# controller.net
KiCad netlist of a schematic drawn in EAGLE
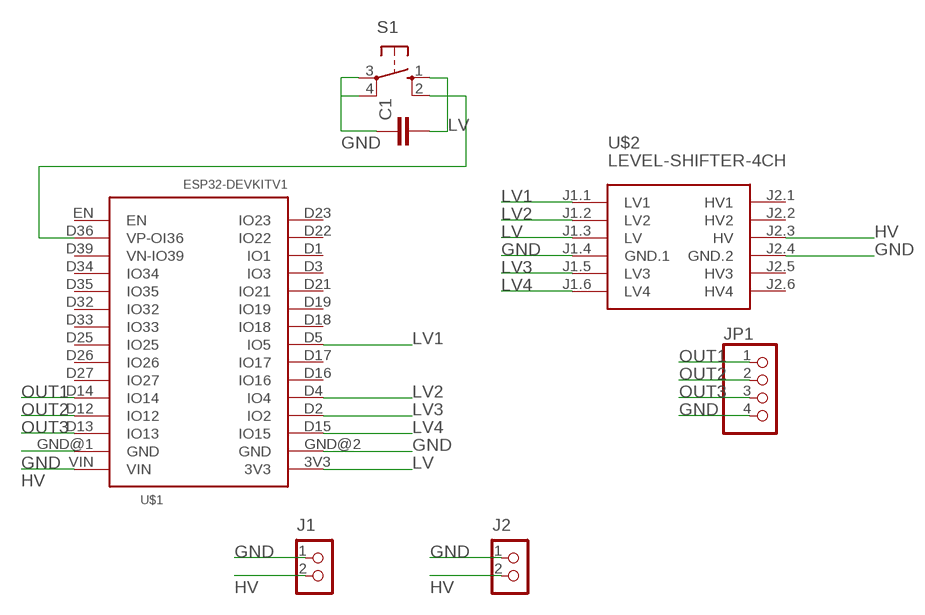
[diagram p0: schematic, sheet 1]

(export (version "E")
  (design (tool "Eeschema 10.0.6"))
  (components
    (comp (ref "C1")
      (value "C-EU025-025X050")
      (footprint "eagle-import:C025-025X050")
      (libsource (lib "eagle-import") (part "C-EU025-025X050"))
    )
    (comp (ref "J1")
      (value "CON_TERMINAL_BLOCK_02-5MM")
      (footprint "eagle-import:TERMINAL_BLOCK_2P_5")
      (libsource (lib "eagle-import") (part "CON_TERMINAL_BLOCK_02-5MM"))
    )
    (comp (ref "J2")
      (value "CON_TERMINAL_BLOCK_02-5MM")
      (footprint "eagle-import:TERMINAL_BLOCK_2P_5")
      (libsource (lib "eagle-import") (part "CON_TERMINAL_BLOCK_02-5MM"))
    )
    (comp (ref "JP1")
      (value "PINHD-1X4")
      (footprint "eagle-import:1X04")
      (libsource (lib "eagle-import") (part "PINHD-1X4"))
    )
    (comp (ref "S1")
      (value "10-XX")
      (footprint "eagle-import:B3F-10XX")
      (fields (field (name "MPN") "B3F-1000"))
      (libsource (lib "eagle-import") (part "10-XX"))
    )
    (comp (ref "U$1")
      (value "ESP32DEVKITV1")
      (footprint "eagle-import:ESP32-DEVKITV1")
      (libsource (lib "eagle-import") (part "ESP32DEVKITV1"))
    )
    (comp (ref "U$2")
      (value "LEVEL-SHIFTER-4CH")
      (footprint "eagle-import:LEVEL-SHIFTER-4CH")
      (libsource (lib "eagle-import") (part "LEVEL-SHIFTER-4CH"))
    )
  )
  (nets
    (net (code "1") (name "/GND") (class "Default")
      (node (ref "C1") (pin "1") (pinfunction "1_1") (pintype "passive"))
      (node (ref "J1") (pin "1") (pinfunction "1_1") (pintype "passive"))
      (node (ref "J2") (pin "1") (pinfunction "1_1") (pintype "passive"))
      (node (ref "JP1") (pin "4") (pinfunction "4_4") (pintype "passive"))
      (node (ref "S1") (pin "3") (pinfunction "P_3") (pintype "passive"))
      (node (ref "S1") (pin "4") (pinfunction "P1_4") (pintype "passive"))
      (node (ref "U$1") (pin "GND@1") (pinfunction "GND_GND@1") (pintype "bidirectional"))
      (node (ref "U$1") (pin "GND@2") (pinfunction "GND_GND@2") (pintype "bidirectional"))
      (node (ref "U$2") (pin "J1.4") (pinfunction "GND.1_J1.4") (pintype "power_in"))
      (node (ref "U$2") (pin "J2.4") (pinfunction "GND.2_J2.4") (pintype "power_in"))
    )
    (net (code "2") (name "/HV") (class "Default")
      (node (ref "J1") (pin "2") (pinfunction "2_2") (pintype "passive"))
      (node (ref "J2") (pin "2") (pinfunction "2_2") (pintype "passive"))
      (node (ref "U$1") (pin "VIN") (pinfunction "VIN_VIN") (pintype "bidirectional"))
      (node (ref "U$2") (pin "J2.3") (pinfunction "HV_J2.3") (pintype "power_in"))
    )
    (net (code "3") (name "/LV") (class "Default")
      (node (ref "C1") (pin "2") (pinfunction "2_2") (pintype "passive"))
      (node (ref "S1") (pin "1") (pinfunction "S_1") (pintype "passive"))
      (node (ref "S1") (pin "2") (pinfunction "S1_2") (pintype "passive"))
      (node (ref "U$1") (pin "3V3") (pinfunction "3V3_3V3") (pintype "bidirectional"))
      (node (ref "U$1") (pin "D36") (pinfunction "VP-OI36_D36") (pintype "bidirectional"))
      (node (ref "U$2") (pin "J1.3") (pinfunction "LV_J1.3") (pintype "power_in"))
    )
    (net (code "4") (name "/LV1") (class "Default")
      (node (ref "U$1") (pin "D5") (pinfunction "IO5_D5") (pintype "bidirectional"))
      (node (ref "U$2") (pin "J1.1") (pinfunction "LV1_J1.1") (pintype "bidirectional"))
    )
    (net (code "5") (name "/LV2") (class "Default")
      (node (ref "U$1") (pin "D4") (pinfunction "IO4_D4") (pintype "bidirectional"))
      (node (ref "U$2") (pin "J1.2") (pinfunction "LV2_J1.2") (pintype "bidirectional"))
    )
    (net (code "6") (name "/LV3") (class "Default")
      (node (ref "U$1") (pin "D2") (pinfunction "IO2_D2") (pintype "bidirectional"))
      (node (ref "U$2") (pin "J1.5") (pinfunction "LV3_J1.5") (pintype "bidirectional"))
    )
    (net (code "7") (name "/LV4") (class "Default")
      (node (ref "U$1") (pin "D15") (pinfunction "IO15_D15") (pintype "bidirectional"))
      (node (ref "U$2") (pin "J1.6") (pinfunction "LV4_J1.6") (pintype "bidirectional"))
    )
    (net (code "8") (name "/OUT1") (class "Default")
      (node (ref "JP1") (pin "1") (pinfunction "1_1") (pintype "passive"))
      (node (ref "U$1") (pin "D14") (pinfunction "IO14_D14") (pintype "bidirectional"))
    )
    (net (code "9") (name "/OUT2") (class "Default")
      (node (ref "JP1") (pin "2") (pinfunction "2_2") (pintype "passive"))
      (node (ref "U$1") (pin "D12") (pinfunction "IO12_D12") (pintype "bidirectional"))
    )
    (net (code "10") (name "/OUT3") (class "Default")
      (node (ref "JP1") (pin "3") (pinfunction "3_3") (pintype "passive"))
      (node (ref "U$1") (pin "D13") (pinfunction "IO13_D13") (pintype "bidirectional"))
    )
    (net (code "11") (name "unconnected-(U$1-IO1-PadD1)") (class "Default")
      (node (ref "U$1") (pin "D1") (pinfunction "IO1_D1") (pintype "bidirectional"))
    )
    (net (code "12") (name "unconnected-(U$1-IO3-PadD3)") (class "Default")
      (node (ref "U$1") (pin "D3") (pinfunction "IO3_D3") (pintype "bidirectional"))
    )
    (net (code "13") (name "unconnected-(U$1-IO16-PadD16)") (class "Default")
      (node (ref "U$1") (pin "D16") (pinfunction "IO16_D16") (pintype "bidirectional"))
    )
    (net (code "14") (name "unconnected-(U$1-IO17-PadD17)") (class "Default")
      (node (ref "U$1") (pin "D17") (pinfunction "IO17_D17") (pintype "bidirectional"))
    )
    (net (code "15") (name "unconnected-(U$1-IO18-PadD18)") (class "Default")
      (node (ref "U$1") (pin "D18") (pinfunction "IO18_D18") (pintype "bidirectional"))
    )
    (net (code "16") (name "unconnected-(U$1-IO19-PadD19)") (class "Default")
      (node (ref "U$1") (pin "D19") (pinfunction "IO19_D19") (pintype "bidirectional"))
    )
    (net (code "17") (name "unconnected-(U$1-IO21-PadD21)") (class "Default")
      (node (ref "U$1") (pin "D21") (pinfunction "IO21_D21") (pintype "bidirectional"))
    )
    (net (code "18") (name "unconnected-(U$1-IO22-PadD22)") (class "Default")
      (node (ref "U$1") (pin "D22") (pinfunction "IO22_D22") (pintype "bidirectional"))
    )
    (net (code "19") (name "unconnected-(U$1-IO23-PadD23)") (class "Default")
      (node (ref "U$1") (pin "D23") (pinfunction "IO23_D23") (pintype "bidirectional"))
    )
    (net (code "20") (name "unconnected-(U$1-IO25-PadD25)") (class "Default")
      (node (ref "U$1") (pin "D25") (pinfunction "IO25_D25") (pintype "bidirectional"))
    )
    (net (code "21") (name "unconnected-(U$1-IO26-PadD26)") (class "Default")
      (node (ref "U$1") (pin "D26") (pinfunction "IO26_D26") (pintype "bidirectional"))
    )
    (net (code "22") (name "unconnected-(U$1-IO27-PadD27)") (class "Default")
      (node (ref "U$1") (pin "D27") (pinfunction "IO27_D27") (pintype "bidirectional"))
    )
    (net (code "23") (name "unconnected-(U$1-IO32-PadD32)") (class "Default")
      (node (ref "U$1") (pin "D32") (pinfunction "IO32_D32") (pintype "bidirectional"))
    )
    (net (code "24") (name "unconnected-(U$1-IO33-PadD33)") (class "Default")
      (node (ref "U$1") (pin "D33") (pinfunction "IO33_D33") (pintype "bidirectional"))
    )
    (net (code "25") (name "unconnected-(U$1-IO34-PadD34)") (class "Default")
      (node (ref "U$1") (pin "D34") (pinfunction "IO34_D34") (pintype "bidirectional"))
    )
    (net (code "26") (name "unconnected-(U$1-IO35-PadD35)") (class "Default")
      (node (ref "U$1") (pin "D35") (pinfunction "IO35_D35") (pintype "bidirectional"))
    )
    (net (code "27") (name "unconnected-(U$1-PadEN)") (class "Default")
      (node (ref "U$1") (pin "EN") (pinfunction "EN_EN") (pintype "bidirectional"))
    )
    (net (code "28") (name "unconnected-(U$1-VN-IO39-PadD39)") (class "Default")
      (node (ref "U$1") (pin "D39") (pinfunction "VN-IO39_D39") (pintype "bidirectional"))
    )
    (net (code "29") (name "unconnected-(U$2-HV1-PadJ2.1)") (class "Default")
      (node (ref "U$2") (pin "J2.1") (pinfunction "HV1_J2.1") (pintype "bidirectional"))
    )
    (net (code "30") (name "unconnected-(U$2-HV2-PadJ2.2)") (class "Default")
      (node (ref "U$2") (pin "J2.2") (pinfunction "HV2_J2.2") (pintype "bidirectional"))
    )
    (net (code "31") (name "unconnected-(U$2-HV3-PadJ2.5)") (class "Default")
      (node (ref "U$2") (pin "J2.5") (pinfunction "HV3_J2.5") (pintype "bidirectional"))
    )
    (net (code "32") (name "unconnected-(U$2-HV4-PadJ2.6)") (class "Default")
      (node (ref "U$2") (pin "J2.6") (pinfunction "HV4_J2.6") (pintype "bidirectional"))
    )
  )
)
